# TEST-MODULE.net
KiCad netlist of a schematic drawn in Altium Designer
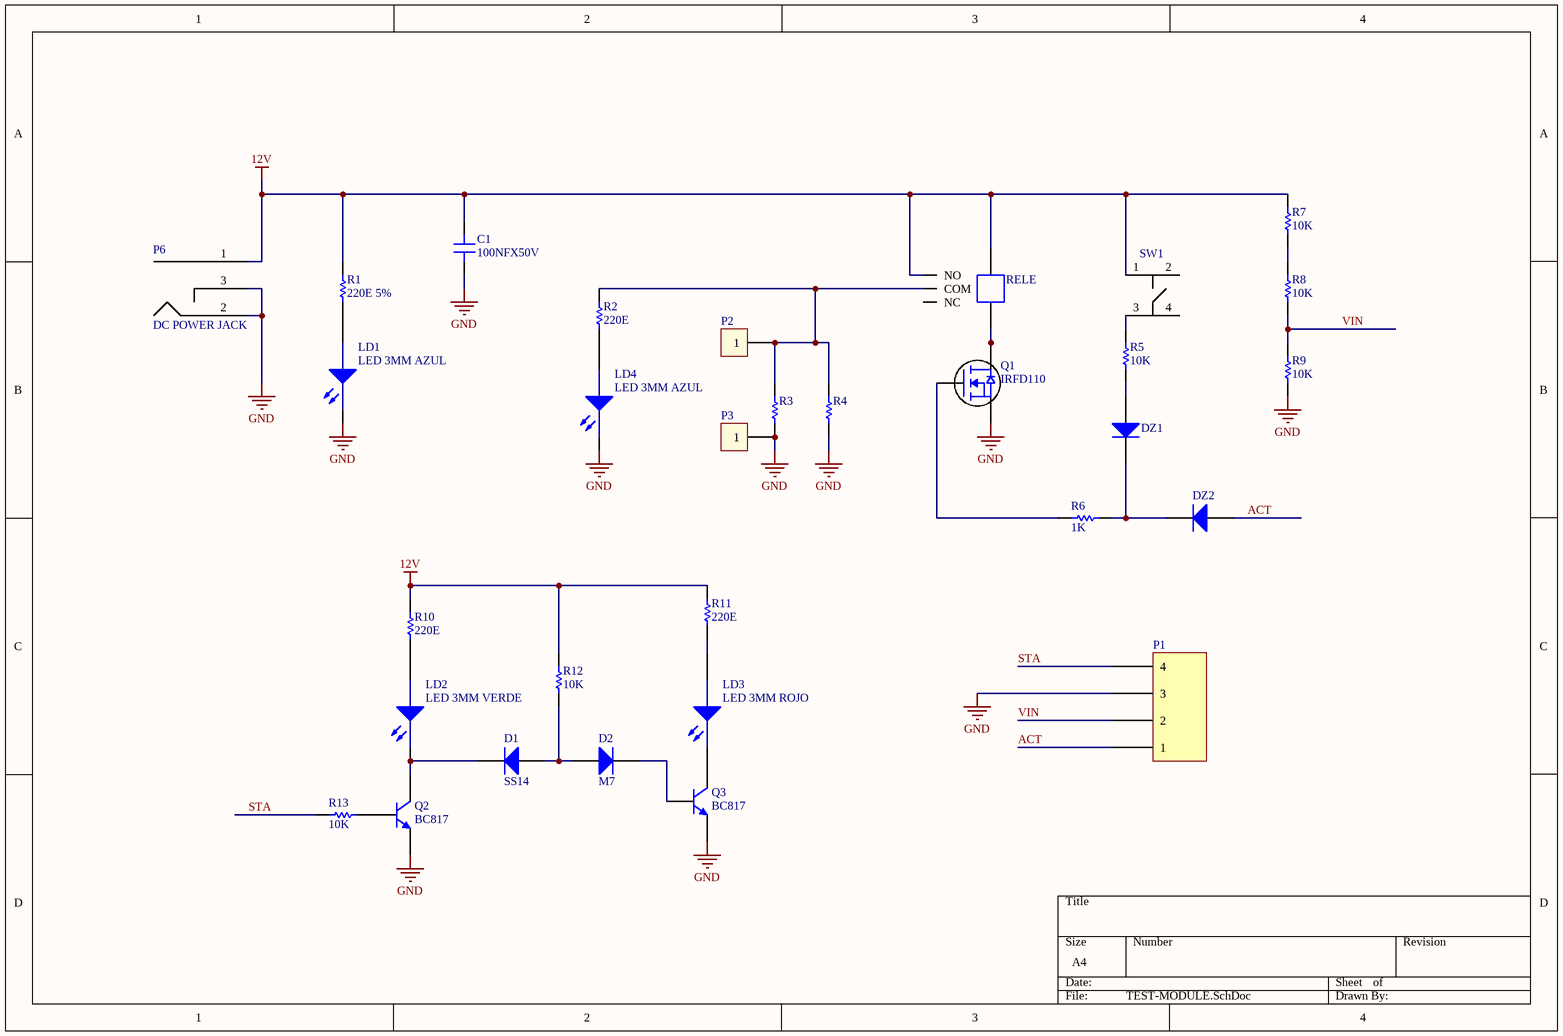
[diagram p0: TEST-MODULE.SchDoc]

(export (version "E")
  (design (tool "Eeschema 10.0.6"))
  (components
    (comp (ref "C1")
      (value "100NFX50V")
      (footprint "CAP.SMD.0805")
      (description "100NFX50V X7R 10% CER.MULT. SMD 0805")
      (libsource (lib "Libreria-Capacitores") (part "Capacitor 100NFX50V X7R 10% CER.MULT. SMD 0805"))
    )
    (comp (ref "D1")
      (value "SS14")
      (footprint "Diode-SMD-SMA")
      (description "M7 DIODO 1A 1000V SMD-SMA (1N4007) XYG")
      (libsource (lib "Libreria-Diodos") (part "Diodo M7 DIODO 1A 1000V SMD-SMA (1N4007) XYG"))
    )
    (comp (ref "D2")
      (value "M7")
      (footprint "Diode-SMD-SMA")
      (description "M7 DIODO 1A 1000V SMD-SMA (1N4007) XYG")
      (libsource (lib "Libreria-Diodos") (part "Diodo M7 DIODO 1A 1000V SMD-SMA (1N4007) XYG"))
    )
    (comp (ref "DZ1")
      (value "M7 DIODO 1A 1000V SMD-SMA (1N4007) XYG")
      (footprint "Diode-SMD-SMA")
      (libsource (lib "Libreria-Diodos") (part "Diodo M7 DIODO 1A 1000V SMD-SMA (1N4007) XYG"))
    )
    (comp (ref "DZ2")
      (value "M7 DIODO 1A 1000V SMD-SMA (1N4007) XYG")
      (footprint "Diode-SMD-SMA")
      (libsource (lib "Libreria-Diodos") (part "Diodo M7 DIODO 1A 1000V SMD-SMA (1N4007) XYG"))
    )
    (comp (ref "LD1")
      (value "LED 3MM AZUL")
      (footprint "LED 3MM AZUL")
      (description "LED 3MM AZUL WC SUPER BRILLO 1250mcd 30潞 204-10SUBC/C470/S400-A6 PATAS 14MM")
      (libsource (lib "Libreria-LEDs") (part "LED 3MM AZUL WC SUPER BRILLO 1250mcd 30潞 204-10SUBC/C470/S400-A6 PATAS 14MM"))
    )
    (comp (ref "LD2")
      (value "LED 3MM VERDE")
      (footprint "LED 3MM VERDE")
      (description "LED 3MM VERDE WC SUPER BRILLO 15000mcd 26潞")
      (libsource (lib "Libreria-LEDs") (part "LED 3MM VERDE WC SUPER BRILLO 15000mcd 26潞"))
    )
    (comp (ref "LD3")
      (value "LED 3MM ROJO")
      (footprint "LED 3MM ROJO")
      (description "LED 3MM ROJO WC SUPER BRILLO 2000mcd 26潞")
      (libsource (lib "Libreria-LEDs") (part "LED 3MM ROJO WC SUPER BRILLO 2000mcd 26潞"))
    )
    (comp (ref "LD4")
      (value "LED 3MM AZUL")
      (footprint "LED 3MM AZUL")
      (description "LED 3MM AZUL WC SUPER BRILLO 1250mcd 30潞 204-10SUBC/C470/S400-A6 PATAS 14MM")
      (libsource (lib "Libreria-LEDs") (part "LED 3MM AZUL WC SUPER BRILLO 1250mcd 30潞 204-10SUBC/C470/S400-A6 PATAS 14MM"))
    )
    (comp (ref "P1")
      (value "CONECTOR PWXXS MA-04 VERTICAL P=3.96MM PW0")
      (footprint "CONECTOR PWXXS MA-04 VERTICAL P=3.96MM")
      (libsource (lib "Libreria-Conectores") (part "CONECTOR PWXXS MA-04 VERTICAL P=3.96MM PW04S"))
    )
    (comp (ref "P2")
      (value "IDC-MA-THT-1X1-P2.54MM-L11")
      (footprint "IDC-MA-THT-1X1-P2.54MM-L11")
      (libsource (lib "Libreria-Conectores") (part "IDC-MA-THT-1X1-P2.54MM-L11"))
    )
    (comp (ref "P3")
      (value "IDC-MA-THT-1X1-P2.54MM-L11")
      (footprint "IDC-MA-THT-1X1-P2.54MM-L11")
      (libsource (lib "Libreria-Conectores") (part "IDC-MA-THT-1X1-P2.54MM-L11"))
    )
    (comp (ref "P6")
      (value "DC POWER JACK")
      (footprint "VAR-DC-JACK")
      (description "DC POWER JACK 90 GRA. 2MM")
      (libsource (lib "Libreria-Varios") (part "DC POWER JACK 90 GRA. 2MM"))
    )
    (comp (ref "Q1")
      (value "IRFD110")
      (footprint "TRA-IRFD110")
      (description "Transistor MOSFET N IRFD110")
      (libsource (lib "Libreria-Transistores") (part "Transistor MOSFET N IRFD110"))
    )
    (comp (ref "Q2")
      (value "BC817")
      (footprint "NPN.SMD.SOT23")
      (description "BC817-40 TRA.NPN 45V0.5A 0.25W SOT23")
      (libsource (lib "Libreria-Transistores") (part "Transistor BC817-40 TRA.NPN 45V0.5A 0.25W SOT23"))
    )
    (comp (ref "Q3")
      (value "BC817")
      (footprint "NPN.SMD.SOT23")
      (description "BC817-40 TRA.NPN 45V0.5A 0.25W SOT23")
      (libsource (lib "Libreria-Transistores") (part "Transistor BC817-40 TRA.NPN 45V0.5A 0.25W SOT23"))
    )
    (comp (ref "R1")
      (value "220E 5%")
      (footprint "RES.SMD.221")
      (description "220E 5% 0805 1/8W RES.SMD")
      (libsource (lib "Libreria-Resistencias") (part "Resistencia 220E 5% 0805 1/8W"))
    )
    (comp (ref "R2")
      (value "220E")
      (footprint "RES.SMD.221")
      (description "220E 5% 0805 1/8W RES.SMD")
      (libsource (lib "Libreria-Resistencias") (part "Resistencia 220E 5% 0805 1/8W"))
    )
    (comp (ref "R3")
      (value "Resistencia Ceramica 15E 5% 15W SE15 RES.CEM")
      (footprint "RES-CERAMICA-15W")
      (libsource (lib "Libreria-Resistencias") (part "Resistencia Ceramica 15E 5% 15W SE15 RES.CEM"))
    )
    (comp (ref "R4")
      (value "Resistencia Ceramica 15E 5% 15W SE15 RES.CEM")
      (footprint "RES-CERAMICA-15W")
      (libsource (lib "Libreria-Resistencias") (part "Resistencia Ceramica 15E 5% 15W SE15 RES.CEM"))
    )
    (comp (ref "R5")
      (value "10K")
      (footprint "RES.SMD.103")
      (description "10K 5% 0805 1/8W RES.SMD")
      (libsource (lib "Libreria-Resistencias") (part "Resistencia 10K 5% 0805 1/8W"))
    )
    (comp (ref "R6")
      (value "1K")
      (footprint "RES.SMD.102")
      (description "1K 5% 0805 1/8W RES.SMD")
      (libsource (lib "Libreria-Resistencias") (part "Resistencia 1K 5% 0805 1/8W"))
    )
    (comp (ref "R7")
      (value "10K")
      (footprint "RES.SMD.103")
      (description "10K 5% 0805 1/8W RES.SMD")
      (libsource (lib "Libreria-Resistencias") (part "Resistencia 10K 5% 0805 1/8W"))
    )
    (comp (ref "R8")
      (value "10K")
      (footprint "RES.SMD.103")
      (description "10K 5% 0805 1/8W RES.SMD")
      (libsource (lib "Libreria-Resistencias") (part "Resistencia 10K 5% 0805 1/8W"))
    )
    (comp (ref "R9")
      (value "10K")
      (footprint "RES.SMD.103")
      (description "10K 5% 0805 1/8W RES.SMD")
      (libsource (lib "Libreria-Resistencias") (part "Resistencia 10K 5% 0805 1/8W"))
    )
    (comp (ref "R10")
      (value "220E")
      (footprint "RES.SMD.221")
      (description "220E 5% 0805 1/8W RES.SMD")
      (libsource (lib "Libreria-Resistencias") (part "Resistencia 220E 5% 0805 1/8W"))
    )
    (comp (ref "R11")
      (value "220E")
      (footprint "RES.SMD.221")
      (description "220E 5% 0805 1/8W RES.SMD")
      (libsource (lib "Libreria-Resistencias") (part "Resistencia 220E 5% 0805 1/8W"))
    )
    (comp (ref "R12")
      (value "10K")
      (footprint "RES.SMD.103")
      (description "10K 5% 0805 1/8W RES.SMD")
      (libsource (lib "Libreria-Resistencias") (part "Resistencia 10K 5% 0805 1/8W"))
    )
    (comp (ref "R13")
      (value "10K")
      (footprint "RES.SMD.103")
      (description "10K 5% 0805 1/8W RES.SMD")
      (libsource (lib "Libreria-Resistencias") (part "Resistencia 10K 5% 0805 1/8W"))
    )
    (comp (ref "RELE")
      (value "Relay simple inversor 5V 10A")
      (footprint "VAR-RELE-5V10A")
      (libsource (lib "Libreria-Varios") (part "VAR-RELE-5V Relay simple inversor 5V 10A"))
    )
    (comp (ref "SW1")
      (value "TACT-SWITCH")
      (footprint "TACT-SWITCH-THT-4C-06X06-4.3MM")
      (description "TACT-SWITCH-THT-4C-06X06(4.3MM)-JIANFU")
      (libsource (lib "Libreria-Switches") (part "TACT-SWITCH-THT-4C-06X06(4.3MM)-JIANFU"))
    )
  )
  (nets
    (net (code "1") (name "/ACT") (class "Default")
      (node (ref "DZ2") (pin "A") (pinfunction "A_A") (pintype "passive"))
      (node (ref "P1") (pin "1") (pinfunction "1_1") (pintype "passive"))
    )
    (net (code "2") (name "/STA") (class "Default")
      (node (ref "P1") (pin "4") (pinfunction "4_4") (pintype "passive"))
      (node (ref "R13") (pin "1") (pinfunction "1_1") (pintype "passive"))
    )
    (net (code "3") (name "/VIN") (class "Default")
      (node (ref "P1") (pin "2") (pinfunction "2_2") (pintype "passive"))
      (node (ref "R8") (pin "1") (pinfunction "1_1") (pintype "passive"))
      (node (ref "R9") (pin "2") (pinfunction "2_2") (pintype "passive"))
    )
    (net (code "4") (name "12V") (class "Default")
      (node (ref "C1") (pin "2") (pinfunction "2_2") (pintype "passive"))
      (node (ref "P6") (pin "1") (pinfunction "1_1") (pintype "passive"))
      (node (ref "R1") (pin "2") (pinfunction "2_2") (pintype "passive"))
      (node (ref "R10") (pin "2") (pinfunction "2_2") (pintype "passive"))
      (node (ref "R11") (pin "2") (pinfunction "2_2") (pintype "passive"))
      (node (ref "R12") (pin "2") (pinfunction "2_2") (pintype "passive"))
      (node (ref "R7") (pin "2") (pinfunction "2_2") (pintype "passive"))
      (node (ref "RELE") (pin "2") (pinfunction "2_2") (pintype "passive"))
      (node (ref "RELE") (pin "4") (pinfunction "NO_4") (pintype "passive"))
      (node (ref "SW1") (pin "1") (pinfunction "1_1") (pintype "passive"))
    )
    (net (code "5") (name "GND") (class "Default")
      (node (ref "C1") (pin "1") (pinfunction "1_1") (pintype "passive"))
      (node (ref "LD1") (pin "K") (pinfunction "KB_K") (pintype "passive"))
      (node (ref "LD4") (pin "K") (pinfunction "KB_K") (pintype "passive"))
      (node (ref "P1") (pin "3") (pinfunction "3_3") (pintype "passive"))
      (node (ref "P3") (pin "1") (pinfunction "1_1") (pintype "passive"))
      (node (ref "P6") (pin "2") (pinfunction "2_2") (pintype "passive"))
      (node (ref "P6") (pin "3") (pinfunction "3_3") (pintype "passive"))
      (node (ref "Q1") (pin "4") (pinfunction "4_4") (pintype "passive"))
      (node (ref "Q2") (pin "2") (pinfunction "E_2") (pintype "passive"))
      (node (ref "Q3") (pin "2") (pinfunction "E_2") (pintype "passive"))
      (node (ref "R3") (pin "1") (pinfunction "1_1") (pintype "passive"))
      (node (ref "R4") (pin "1") (pinfunction "1_1") (pintype "passive"))
      (node (ref "R9") (pin "1") (pinfunction "1_1") (pintype "passive"))
    )
    (net (code "6") (name "Net-(D1-PadA)") (class "Default")
      (node (ref "D1") (pin "A") (pinfunction "A_A") (pintype "passive"))
      (node (ref "D2") (pin "A") (pinfunction "A_A") (pintype "passive"))
      (node (ref "R12") (pin "1") (pinfunction "1_1") (pintype "passive"))
    )
    (net (code "7") (name "Net-(DZ1-PadA)") (class "Default")
      (node (ref "DZ1") (pin "A") (pinfunction "A_A") (pintype "passive"))
      (node (ref "R5") (pin "1") (pinfunction "1_1") (pintype "passive"))
    )
    (net (code "8") (name "Net-(DZ1-PadK)") (class "Default")
      (node (ref "DZ1") (pin "K") (pinfunction "K_K") (pintype "passive"))
      (node (ref "DZ2") (pin "K") (pinfunction "K_K") (pintype "passive"))
      (node (ref "R6") (pin "2") (pinfunction "2_2") (pintype "passive"))
    )
    (net (code "9") (name "Net-(LD1-AB)") (class "Default")
      (node (ref "LD1") (pin "A") (pinfunction "AB_A") (pintype "passive"))
      (node (ref "R1") (pin "1") (pinfunction "1_1") (pintype "passive"))
    )
    (net (code "10") (name "Net-(LD2-AB)") (class "Default")
      (node (ref "LD2") (pin "A") (pinfunction "AB_A") (pintype "passive"))
      (node (ref "R10") (pin "1") (pinfunction "1_1") (pintype "passive"))
    )
    (net (code "11") (name "Net-(LD2-KB)") (class "Default")
      (node (ref "D1") (pin "K") (pinfunction "K_K") (pintype "passive"))
      (node (ref "LD2") (pin "K") (pinfunction "KB_K") (pintype "passive"))
      (node (ref "Q2") (pin "3") (pinfunction "C_3") (pintype "passive"))
    )
    (net (code "12") (name "Net-(LD3-AB)") (class "Default")
      (node (ref "LD3") (pin "A") (pinfunction "AB_A") (pintype "passive"))
      (node (ref "R11") (pin "1") (pinfunction "1_1") (pintype "passive"))
    )
    (net (code "13") (name "Net-(LD3-KB)") (class "Default")
      (node (ref "LD3") (pin "K") (pinfunction "KB_K") (pintype "passive"))
      (node (ref "Q3") (pin "3") (pinfunction "C_3") (pintype "passive"))
    )
    (net (code "14") (name "Net-(LD4-AB)") (class "Default")
      (node (ref "LD4") (pin "A") (pinfunction "AB_A") (pintype "passive"))
      (node (ref "R2") (pin "1") (pinfunction "1_1") (pintype "passive"))
    )
    (net (code "15") (name "Net-(Q1-Pad1)") (class "Default")
      (node (ref "Q1") (pin "1") (pinfunction "1_1") (pintype "passive"))
      (node (ref "Q1") (pin "2") (pinfunction "2_2") (pintype "passive"))
      (node (ref "RELE") (pin "1") (pinfunction "1_1") (pintype "passive"))
    )
    (net (code "16") (name "Net-(Q1-Pad3)") (class "Default")
      (node (ref "Q1") (pin "3") (pinfunction "3_3") (pintype "passive"))
      (node (ref "R6") (pin "1") (pinfunction "1_1") (pintype "passive"))
    )
    (net (code "17") (name "Net-(Q2-B)") (class "Default")
      (node (ref "Q2") (pin "1") (pinfunction "B_1") (pintype "passive"))
      (node (ref "R13") (pin "2") (pinfunction "2_2") (pintype "passive"))
    )
    (net (code "18") (name "Net-(Q3-B)") (class "Default")
      (node (ref "D2") (pin "K") (pinfunction "K_K") (pintype "passive"))
      (node (ref "Q3") (pin "1") (pinfunction "B_1") (pintype "passive"))
    )
    (net (code "19") (name "Net-(R5-Pad2)") (class "Default")
      (node (ref "R5") (pin "2") (pinfunction "2_2") (pintype "passive"))
      (node (ref "SW1") (pin "3") (pinfunction "3_3") (pintype "passive"))
    )
    (net (code "20") (name "Net-(R7-Pad1)") (class "Default")
      (node (ref "R7") (pin "1") (pinfunction "1_1") (pintype "passive"))
      (node (ref "R8") (pin "2") (pinfunction "2_2") (pintype "passive"))
    )
    (net (code "21") (name "Net-(RELE-COM)") (class "Default")
      (node (ref "P2") (pin "1") (pinfunction "1_1") (pintype "passive"))
      (node (ref "R2") (pin "2") (pinfunction "2_2") (pintype "passive"))
      (node (ref "R3") (pin "2") (pinfunction "2_2") (pintype "passive"))
      (node (ref "R4") (pin "2") (pinfunction "2_2") (pintype "passive"))
      (node (ref "RELE") (pin "3") (pinfunction "COM_3") (pintype "passive"))
    )
    (net (code "22") (name "unconnected-(RELE-NC-Pad5)") (class "Default")
      (node (ref "RELE") (pin "5") (pinfunction "NC_5") (pintype "passive"))
    )
    (net (code "23") (name "unconnected-(SW1-Pad2)") (class "Default")
      (node (ref "SW1") (pin "2") (pinfunction "2_2") (pintype "passive"))
    )
    (net (code "24") (name "unconnected-(SW1-Pad4)") (class "Default")
      (node (ref "SW1") (pin "4") (pinfunction "4_4") (pintype "passive"))
    )
  )
)
